# schmitt-trigger.net
KiCad netlist of a schematic drawn in EAGLE
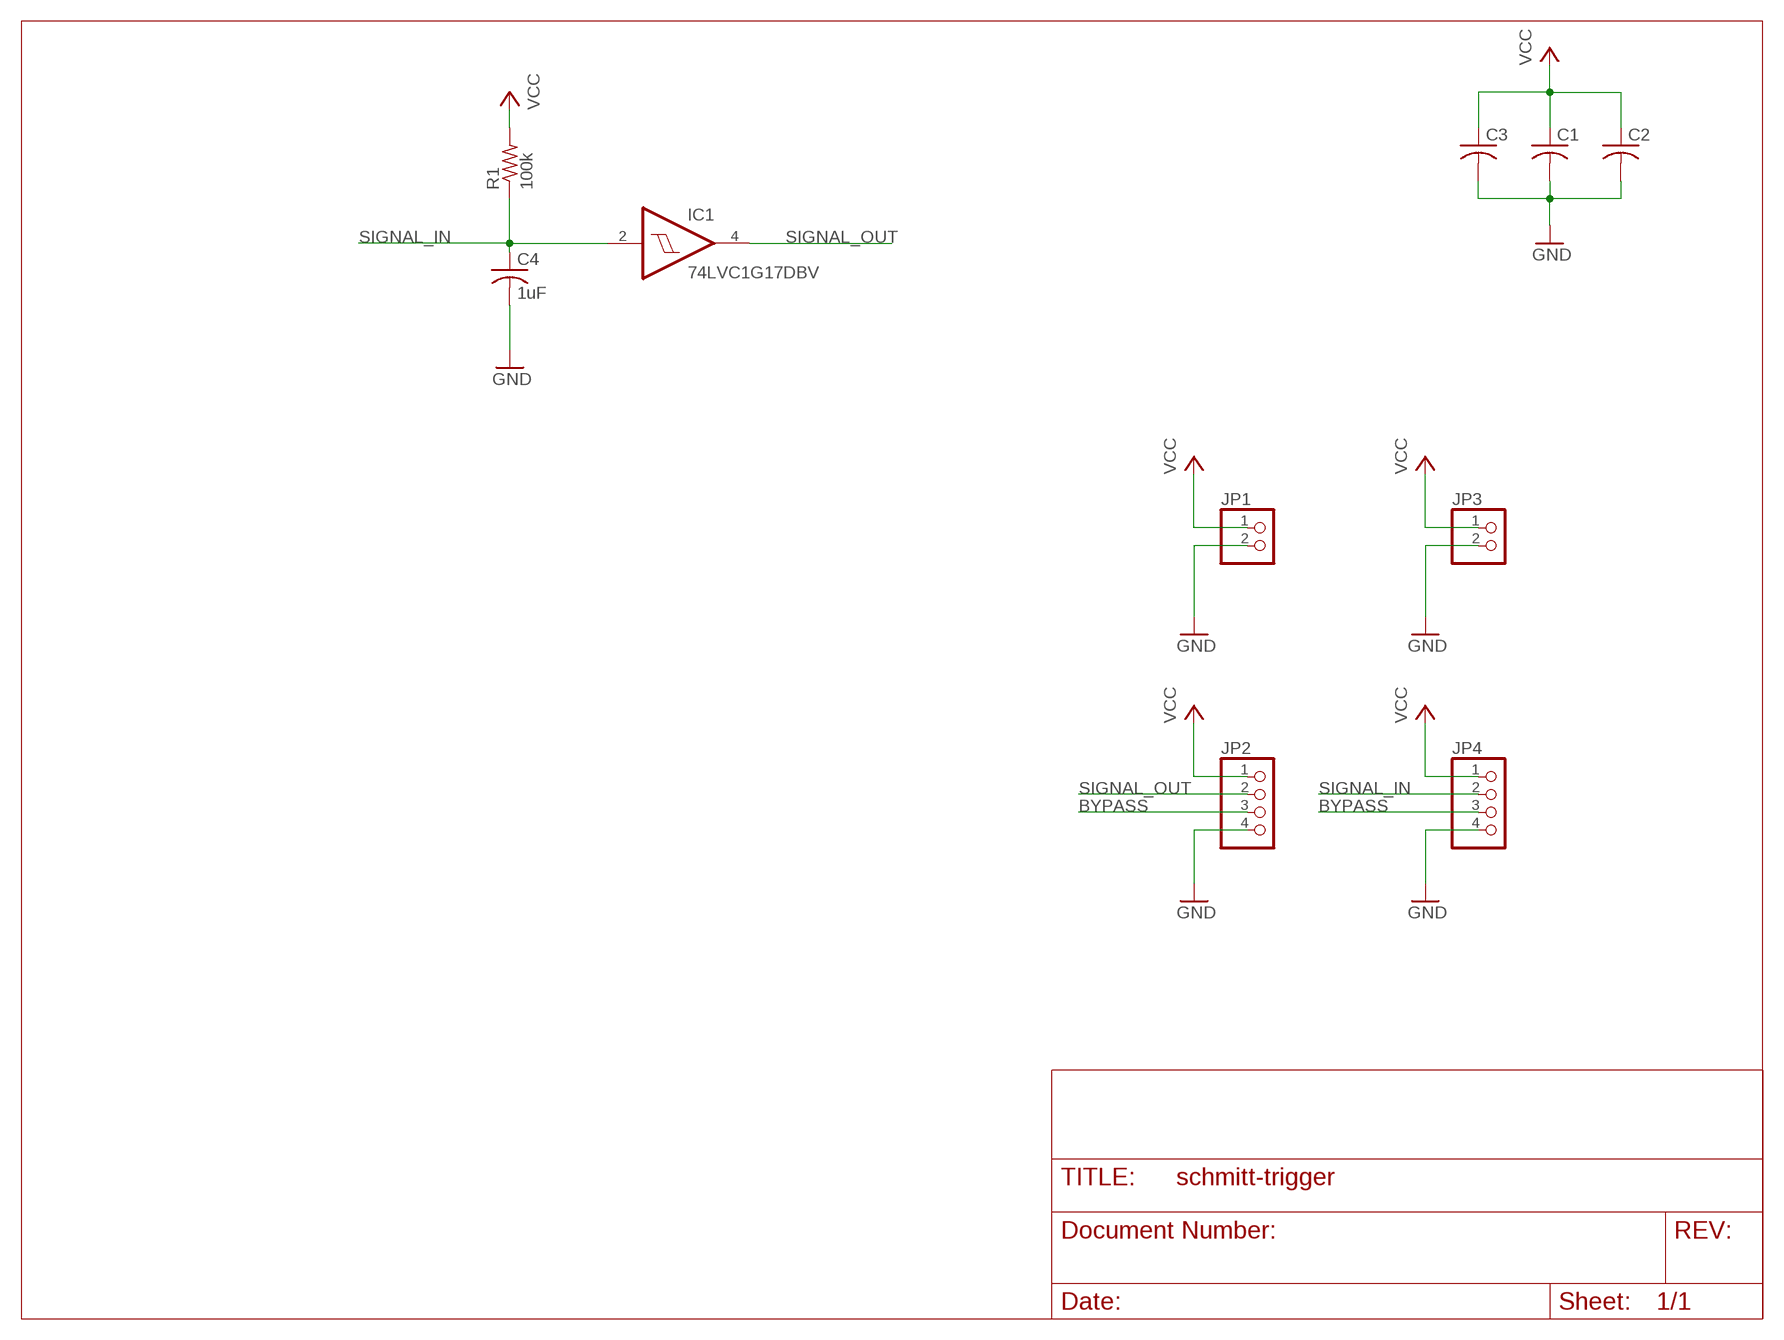
[diagram p0: schematic, sheet 1]

(export (version "E")
  (design (tool "Eeschema 10.0.6"))
  (components
    (comp (ref "C1")
      (value "C-USC0603K")
      (footprint "eagle-import:C0603K")
      (libsource (lib "eagle-import") (part "C-USC0603K"))
    )
    (comp (ref "C2")
      (value "C-USC0603K")
      (footprint "eagle-import:C0603K")
      (libsource (lib "eagle-import") (part "C-USC0603K"))
    )
    (comp (ref "C3")
      (value "C-USC0603K")
      (footprint "eagle-import:C0603K")
      (libsource (lib "eagle-import") (part "C-USC0603K"))
    )
    (comp (ref "C4")
      (value "1uF")
      (footprint "eagle-import:C0603K")
      (libsource (lib "eagle-import") (part "C-USC0603K"))
    )
    (comp (ref "IC1")
      (value "74LVC1G17DBV")
      (footprint "eagle-import:SOT23-5")
      (libsource (lib "eagle-import") (part "741G17DBVLVC"))
    )
    (comp (ref "JP1")
      (value "PINHD-1X2")
      (footprint "eagle-import:1X02")
      (libsource (lib "eagle-import") (part "PINHD-1X2"))
    )
    (comp (ref "JP2")
      (value "PINHD-1X4")
      (footprint "eagle-import:1X04")
      (libsource (lib "eagle-import") (part "PINHD-1X4"))
    )
    (comp (ref "JP3")
      (value "PINHD-1X2")
      (footprint "eagle-import:1X02")
      (libsource (lib "eagle-import") (part "PINHD-1X2"))
    )
    (comp (ref "JP4")
      (value "PINHD-1X4")
      (footprint "eagle-import:1X04")
      (libsource (lib "eagle-import") (part "PINHD-1X4"))
    )
    (comp (ref "R1")
      (value "100k")
      (footprint "eagle-import:R0603")
      (libsource (lib "eagle-import") (part "R-US_R0603"))
    )
  )
  (nets
    (net (code "1") (name "/BYPASS") (class "Default")
      (node (ref "JP2") (pin "3") (pinfunction "3_3") (pintype "passive"))
      (node (ref "JP4") (pin "3") (pinfunction "3_3") (pintype "passive"))
    )
    (net (code "2") (name "/SIGNAL_IN") (class "Default")
      (node (ref "C4") (pin "1") (pinfunction "1_1") (pintype "passive"))
      (node (ref "IC1") (pin "2") (pinfunction "I_2") (pintype "input"))
      (node (ref "JP4") (pin "2") (pinfunction "2_2") (pintype "passive"))
      (node (ref "R1") (pin "1") (pinfunction "1_1") (pintype "passive"))
    )
    (net (code "3") (name "/SIGNAL_OUT") (class "Default")
      (node (ref "IC1") (pin "4") (pinfunction "O_4") (pintype "output"))
      (node (ref "JP2") (pin "2") (pinfunction "2_2") (pintype "passive"))
    )
    (net (code "4") (name "GND") (class "Default")
      (node (ref "C1") (pin "2") (pinfunction "2_2") (pintype "passive"))
      (node (ref "C2") (pin "2") (pinfunction "2_2") (pintype "passive"))
      (node (ref "C3") (pin "2") (pinfunction "2_2") (pintype "passive"))
      (node (ref "C4") (pin "2") (pinfunction "2_2") (pintype "passive"))
      (node (ref "JP1") (pin "2") (pinfunction "2_2") (pintype "passive"))
      (node (ref "JP2") (pin "4") (pinfunction "4_4") (pintype "passive"))
      (node (ref "JP3") (pin "2") (pinfunction "2_2") (pintype "passive"))
      (node (ref "JP4") (pin "4") (pinfunction "4_4") (pintype "passive"))
    )
    (net (code "5") (name "VCC") (class "Default")
      (node (ref "C1") (pin "1") (pinfunction "1_1") (pintype "passive"))
      (node (ref "C2") (pin "1") (pinfunction "1_1") (pintype "passive"))
      (node (ref "C3") (pin "1") (pinfunction "1_1") (pintype "passive"))
      (node (ref "JP1") (pin "1") (pinfunction "1_1") (pintype "passive"))
      (node (ref "JP2") (pin "1") (pinfunction "1_1") (pintype "passive"))
      (node (ref "JP3") (pin "1") (pinfunction "1_1") (pintype "passive"))
      (node (ref "JP4") (pin "1") (pinfunction "1_1") (pintype "passive"))
      (node (ref "R1") (pin "2") (pinfunction "2_2") (pintype "passive"))
    )
  )
)
